# LCD.net
KiCad netlist of a schematic drawn in Altium Designer
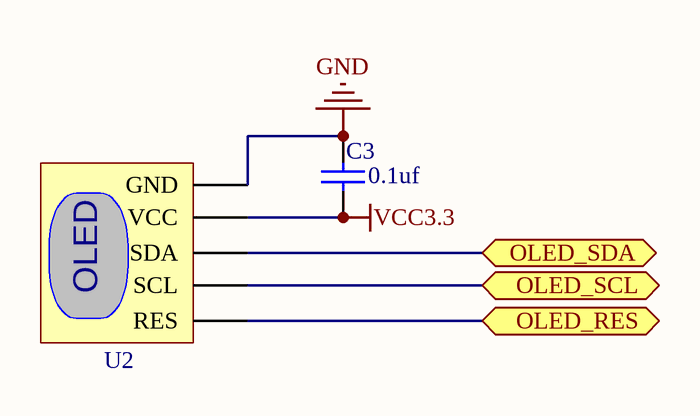
[diagram p0: LCD.SchDoc]

(export (version "E")
  (design (tool "Eeschema 10.0.6"))
  (components
    (comp (ref "C3")
      (value "0.1uf")
      (footprint "0603")
      (fields (field (name "Comment") "Capacitor-0603"))
      (libsource (lib "原理图库") (part "Capacitor-0603"))
    )
    (comp (ref "U2") (value "0.49OLED") (footprint "0.49OLED") (libsource (lib "原理图库") (part "0.49OLED")))
  )
  (nets
    (net (code "1") (name "/OLED_RES") (class "Default")
      (node (ref "U2") (pin "5") (pinfunction "RES_5") (pintype "passive"))
    )
    (net (code "2") (name "/OLED_SCL") (class "Default")
      (node (ref "U2") (pin "4") (pinfunction "SCL_4") (pintype "passive"))
    )
    (net (code "3") (name "/OLED_SDA") (class "Default")
      (node (ref "U2") (pin "3") (pinfunction "SDA_3") (pintype "passive"))
    )
    (net (code "4") (name "GND") (class "Default")
      (node (ref "C3") (pin "2") (pinfunction "2_2") (pintype "passive"))
      (node (ref "U2") (pin "1") (pinfunction "GND_1") (pintype "passive"))
    )
    (net (code "5") (name "VCC3.3") (class "Default")
      (node (ref "C3") (pin "1") (pinfunction "1_1") (pintype "passive"))
      (node (ref "U2") (pin "2") (pinfunction "VCC_2") (pintype "passive"))
    )
  )
)
